# DAC_32CH.net
KiCad netlist of a schematic drawn in Altium Designer
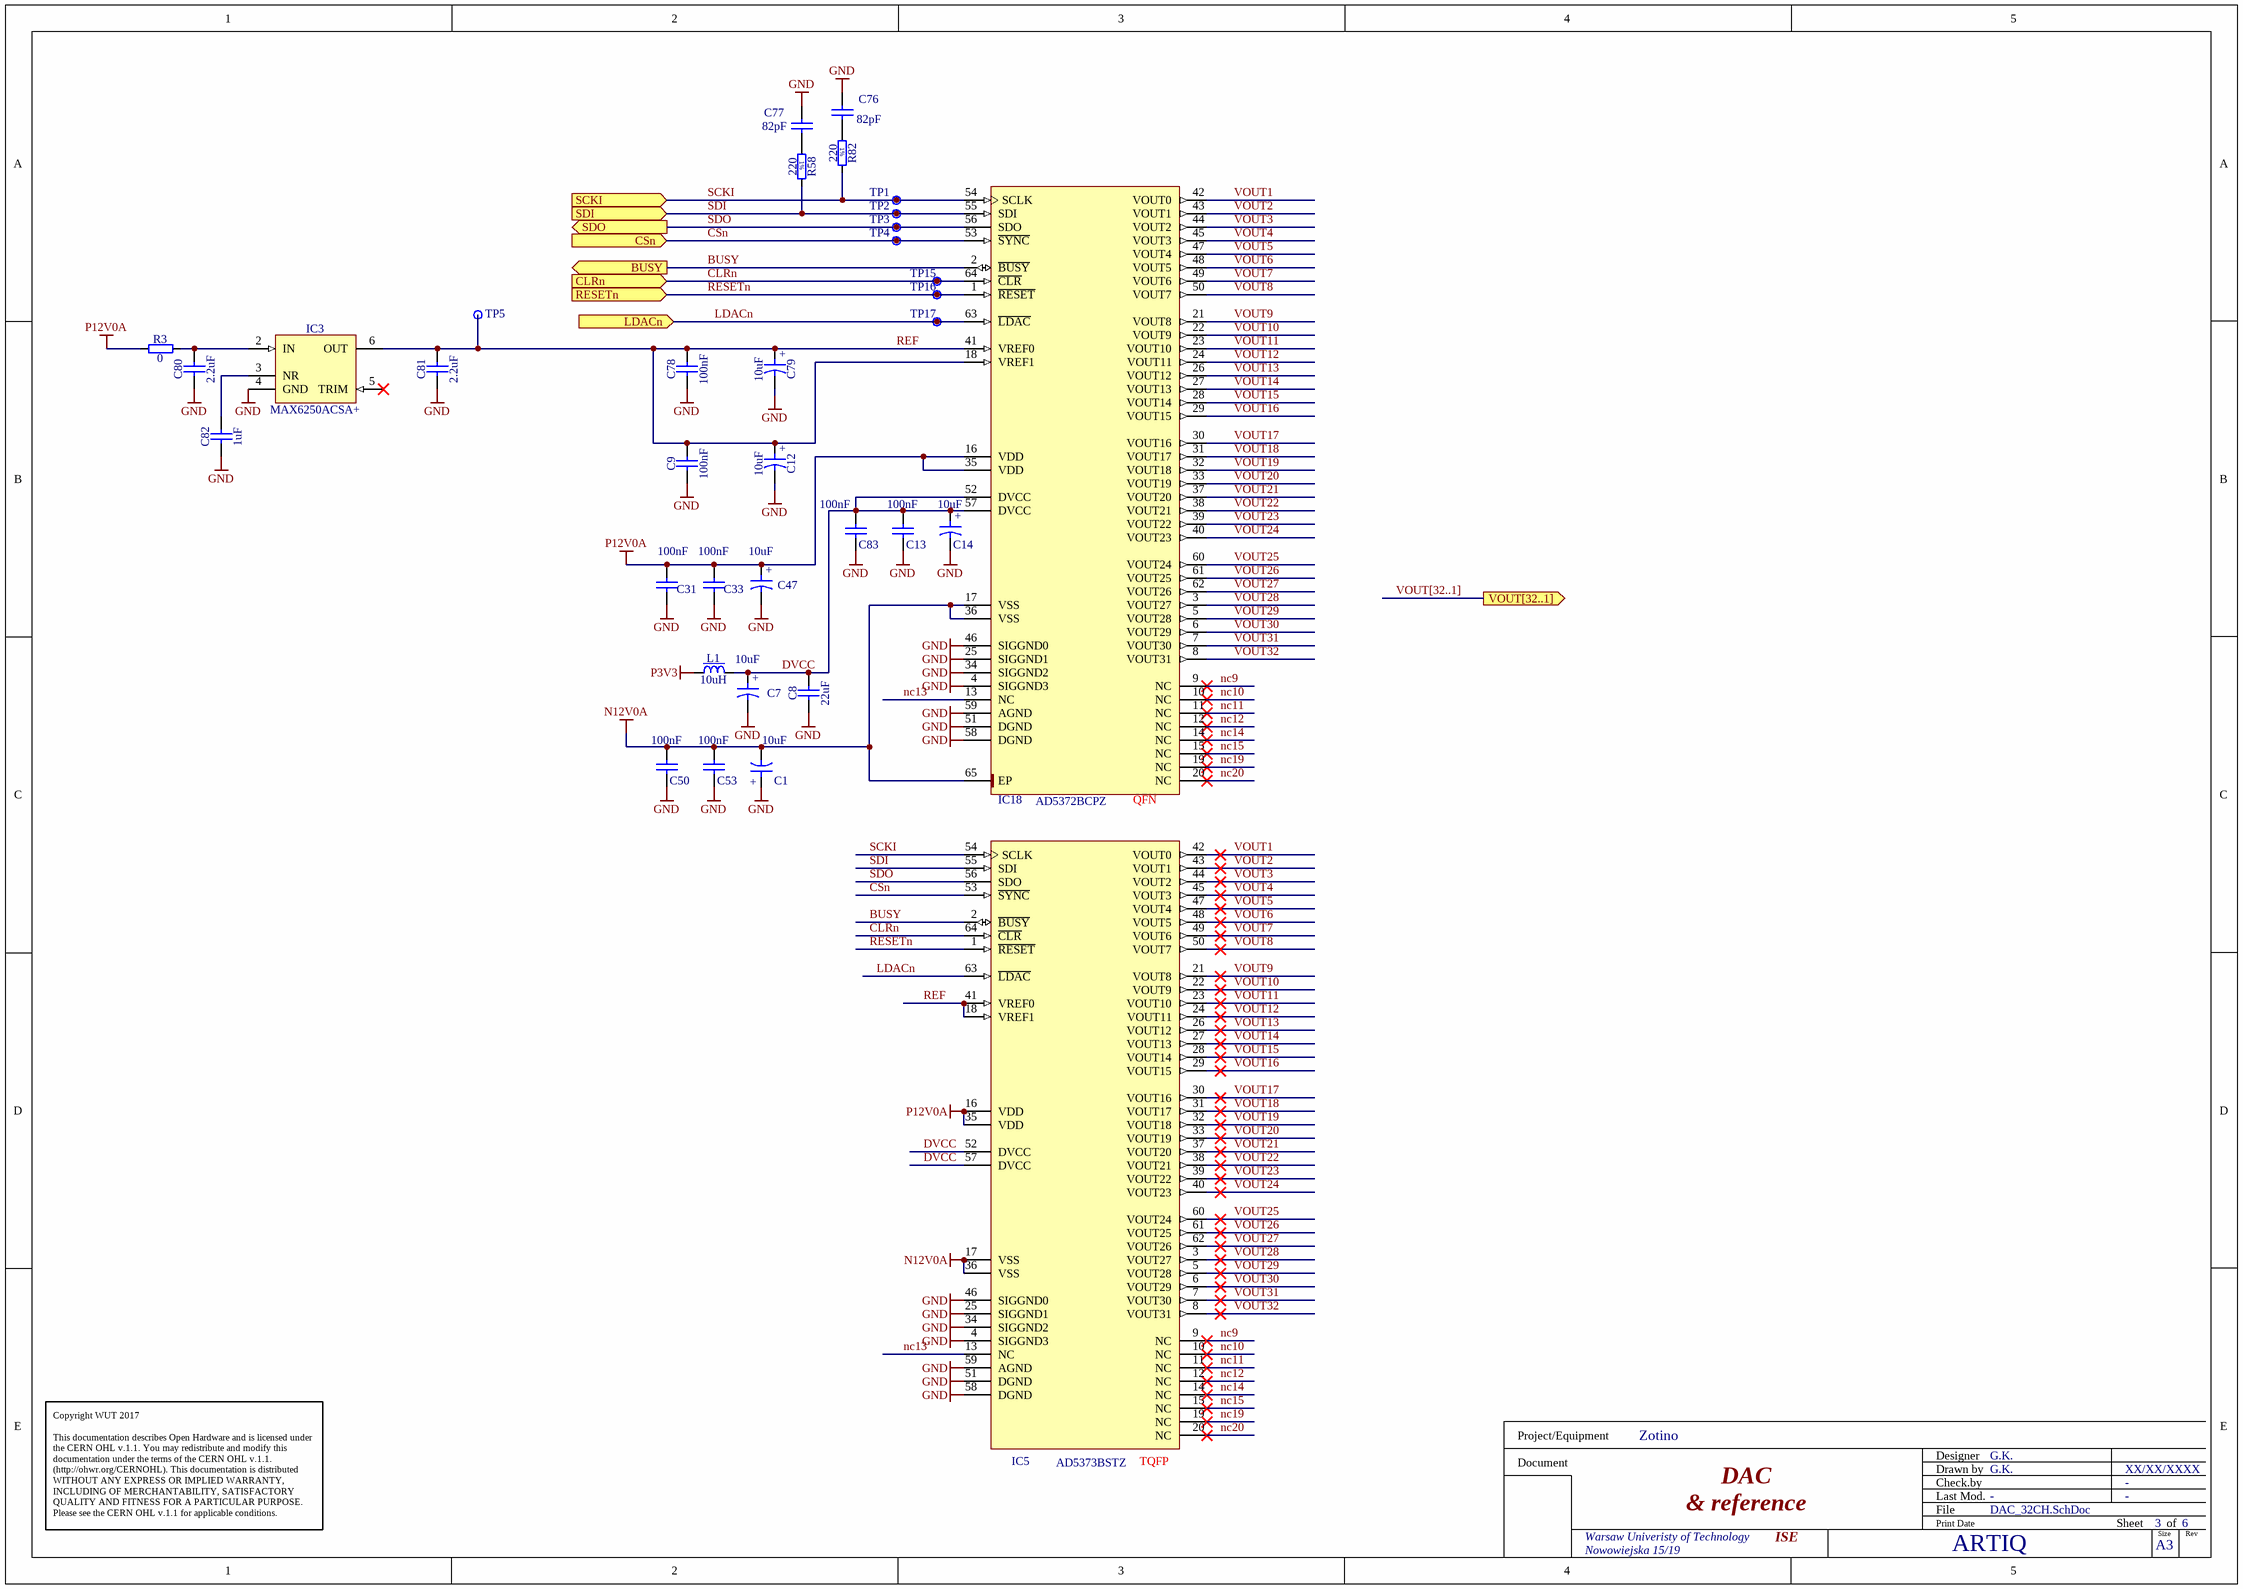
[diagram p0: DAC_32CH.SchDoc]

(export (version "E")
  (design (tool "Eeschema 10.0.6"))
  (components
    (comp (ref "C1")
      (value "10uF")
      (footprint "CAPMP3216X180N")
      (description "Polarised capacitor")
      (fields
        (field (name "PART NUMBER") "CTE3216-18_10UF_16V_20%_AVX_TCJ")
        (field (name "VOLTAGE") "16V")
        (field (name "AUTHOR") "CERN DEM JLC")
      )
      (libsource (lib "Capacitors") (part "Capacitor - polarized"))
    )
    (comp (ref "C7")
      (value "10uF")
      (footprint "CAPMP3216X180N")
      (description "Polarised capacitor")
      (fields
        (field (name "PART NUMBER") "CTE3216-18_10UF_16V_20%_AVX_TCJ")
        (field (name "VOLTAGE") "16V")
        (field (name "AUTHOR") "CERN DEM JLC")
      )
      (libsource (lib "Capacitors") (part "Capacitor - polarized"))
    )
    (comp (ref "C8")
      (value "22uF")
      (footprint "CAPC2012X135N")
      (description "Non-polarised capacitor")
      (fields
        (field (name "PART NUMBER") "CC0805_22UF_16V_10%_X5R")
        (field (name "VOLTAGE") "16V")
        (field (name "AUTHOR") "CERN DEM JLC")
      )
      (libsource (lib "Capacitors") (part "Capacitor - non polarized"))
    )
    (comp (ref "C9")
      (value "100nF")
      (footprint "CAPC1005X55N")
      (description "Non-polarised capacitor")
      (fields
        (field (name "PART NUMBER") "CC0402_100NF_16V_10%_X7R")
        (field (name "VOLTAGE") "16V")
        (field (name "AUTHOR") "CERN DEM JLC")
      )
      (libsource (lib "Capacitors") (part "Capacitor - non polarized"))
    )
    (comp (ref "C12")
      (value "10uF")
      (footprint "CAPMP3216X180N")
      (description "Polarised capacitor")
      (fields
        (field (name "PART NUMBER") "CTE3216-18_10UF_16V_20%_AVX_TCJ")
        (field (name "VOLTAGE") "16V")
        (field (name "AUTHOR") "CERN DEM JLC")
      )
      (libsource (lib "Capacitors") (part "Capacitor - polarized"))
    )
    (comp (ref "C13")
      (value "100nF")
      (footprint "CAPC1005X55N")
      (description "Non-polarised capacitor")
      (fields
        (field (name "PART NUMBER") "CC0402_100NF_16V_10%_X7R")
        (field (name "VOLTAGE") "16V")
        (field (name "AUTHOR") "CERN DEM JLC")
      )
      (libsource (lib "Capacitors") (part "Capacitor - non polarized"))
    )
    (comp (ref "C14")
      (value "10uF")
      (footprint "CAPMP3216X180N")
      (description "Polarised capacitor")
      (fields
        (field (name "PART NUMBER") "CTE3216-18_10UF_16V_20%_AVX_TCJ")
        (field (name "VOLTAGE") "16V")
        (field (name "AUTHOR") "CERN DEM JLC")
      )
      (libsource (lib "Capacitors") (part "Capacitor - polarized"))
    )
    (comp (ref "C31")
      (value "100nF")
      (footprint "CAPC1005X55N")
      (description "Non-polarised capacitor")
      (fields
        (field (name "PART NUMBER") "CC0402_100NF_16V_10%_X7R")
        (field (name "VOLTAGE") "16V")
        (field (name "AUTHOR") "CERN DEM JLC")
      )
      (libsource (lib "Capacitors") (part "Capacitor - non polarized"))
    )
    (comp (ref "C33")
      (value "100nF")
      (footprint "CAPC1005X55N")
      (description "Non-polarised capacitor")
      (fields
        (field (name "PART NUMBER") "CC0402_100NF_16V_10%_X7R")
        (field (name "VOLTAGE") "16V")
        (field (name "AUTHOR") "CERN DEM JLC")
      )
      (libsource (lib "Capacitors") (part "Capacitor - non polarized"))
    )
    (comp (ref "C47")
      (value "10uF")
      (footprint "CAPMP3216X180N")
      (description "Polarised capacitor")
      (fields
        (field (name "PART NUMBER") "CTE3216-18_10UF_16V_20%_AVX_TCJ")
        (field (name "VOLTAGE") "16V")
        (field (name "AUTHOR") "CERN DEM JLC")
      )
      (libsource (lib "Capacitors") (part "Capacitor - polarized"))
    )
    (comp (ref "C50")
      (value "100nF")
      (footprint "CAPC1005X55N")
      (description "Non-polarised capacitor")
      (fields
        (field (name "PART NUMBER") "CC0402_100NF_16V_10%_X7R")
        (field (name "VOLTAGE") "16V")
        (field (name "AUTHOR") "CERN DEM JLC")
      )
      (libsource (lib "Capacitors") (part "Capacitor - non polarized"))
    )
    (comp (ref "C53")
      (value "100nF")
      (footprint "CAPC1005X55N")
      (description "Non-polarised capacitor")
      (fields
        (field (name "PART NUMBER") "CC0402_100NF_16V_10%_X7R")
        (field (name "VOLTAGE") "16V")
        (field (name "AUTHOR") "CERN DEM JLC")
      )
      (libsource (lib "Capacitors") (part "Capacitor - non polarized"))
    )
    (comp (ref "C76")
      (value "82pF")
      (footprint "CAPC1608X87N")
      (description "Non-polarised capacitor")
      (fields
        (field (name "PART NUMBER") "CC0603_82PF_50V_5%_NP0")
        (field (name "VOLTAGE") "50V")
        (field (name "AUTHOR") "CERN DEM JLC")
      )
      (libsource (lib "Capacitors") (part "Capacitor - non polarized"))
    )
    (comp (ref "C77")
      (value "82pF")
      (footprint "CAPC1608X87N")
      (description "Non-polarised capacitor")
      (fields
        (field (name "PART NUMBER") "CC0603_82PF_50V_5%_NP0")
        (field (name "VOLTAGE") "50V")
        (field (name "AUTHOR") "CERN DEM JLC")
      )
      (libsource (lib "Capacitors") (part "Capacitor - non polarized"))
    )
    (comp (ref "C78")
      (value "100nF")
      (footprint "CAPC1005X55N")
      (description "Non-polarised capacitor")
      (fields
        (field (name "PART NUMBER") "CC0402_100NF_16V_10%_X7R")
        (field (name "VOLTAGE") "16V")
        (field (name "AUTHOR") "CERN DEM JLC")
      )
      (libsource (lib "Capacitors") (part "Capacitor - non polarized"))
    )
    (comp (ref "C79")
      (value "10uF")
      (footprint "CAPMP3216X180N")
      (description "Polarised capacitor")
      (fields
        (field (name "PART NUMBER") "CTE3216-18_10UF_16V_20%_AVX_TCJ")
        (field (name "VOLTAGE") "16V")
        (field (name "AUTHOR") "CERN DEM JLC")
      )
      (libsource (lib "Capacitors") (part "Capacitor - polarized"))
    )
    (comp (ref "C80")
      (value "2.2uF")
      (footprint "CAPC1608X87N")
      (description "Non-polarised capacitor")
      (fields
        (field (name "PART NUMBER") "CC0603_2.2UF_16V_10%_X5R")
        (field (name "VOLTAGE") "16V")
        (field (name "AUTHOR") "CERN DEM JLC")
      )
      (libsource (lib "Capacitors") (part "Capacitor - non polarized"))
    )
    (comp (ref "C81")
      (value "2.2uF")
      (footprint "CAPC1608X87N")
      (description "Non-polarised capacitor")
      (fields
        (field (name "PART NUMBER") "CC0603_2.2UF_16V_10%_X5R")
        (field (name "VOLTAGE") "16V")
        (field (name "AUTHOR") "CERN DEM JLC")
      )
      (libsource (lib "Capacitors") (part "Capacitor - non polarized"))
    )
    (comp (ref "C82")
      (value "1uF")
      (footprint "CAPC1608X87N")
      (description "Non-polarised capacitor")
      (fields
        (field (name "PART NUMBER") "CC0603_1UF_25V_10%_X7R")
        (field (name "VOLTAGE") "25V")
        (field (name "AUTHOR") "CERN DEM JLC")
      )
      (libsource (lib "Capacitors") (part "Capacitor - non polarized"))
    )
    (comp (ref "C83")
      (value "100nF")
      (footprint "CAPC1005X55N")
      (description "Non-polarised capacitor")
      (fields
        (field (name "PART NUMBER") "CC0402_100NF_16V_10%_X7R")
        (field (name "VOLTAGE") "16V")
        (field (name "AUTHOR") "CERN DEM JLC")
      )
      (libsource (lib "Capacitors") (part "Capacitor - non polarized"))
    )
    (comp (ref "IC3")
      (value "MAX6250ACSA+")
      (footprint "SOIC127P600X175-8N")
      (description "1ppm/°C, Low-Noise, Precision, +5.000V Voltage Reference")
      (fields (field (name "MANUFACTURER") "MAXIM") (field (name "AUTHOR") "CERN DEM JMW"))
      (libsource (lib "ICs And Semiconductors") (part "MAX6250"))
    )
    (comp (ref "IC5")
      (value "AD5373BSTZ")
      (footprint "TSQFP50P1200X1200X160-64L")
      (description "32-Channel, 16-Bit, Serial Input, Voltage Output Digital-to-Analog Converter")
      (fields (field (name "MANUFACTURER") "ANALOG DEVICES") (field (name "AUTHOR") "GK"))
      (libsource (lib "LIBRARY_SCH") (part "DAC_AD5372_QFP"))
    )
    (comp (ref "IC18")
      (value "AD5372BCPZ")
      (footprint "QFN50P900X900X100-65N-S725")
      (description "32-Channel, 16-Bit, Serial Input, Voltage Output Digital-to-Analog Converter")
      (fields (field (name "MANUFACTURER") "ANALOG DEVICES") (field (name "AUTHOR") "GK"))
      (libsource (lib "LIBRARY_SCH") (part "DAC_AD5372"))
    )
    (comp (ref "L1")
      (value "10uH")
      (footprint "IND_MURATA-PS_8400")
      (description "Inductor With Core")
      (fields
        (field (name "PART NUMBER") "IND_10UH_10%_MURATA-PS_8400")
        (field (name "POWER") "950mA")
        (field (name "AUTHOR") "CERN DEM JLC")
      )
      (libsource (lib "Inductors & Transformers") (part "Inductor With Magnetic core"))
    )
    (comp (ref "R3")
      (value "0")
      (footprint "RESC1005X40N")
      (description "Resistor")
      (fields
        (field (name "PART NUMBER") "R0402_0R_JUMPER")
        (field (name "MANUFACTURER") "GENERIC")
        (field (name "AUTHOR") "CERN DEM JLC")
      )
      (libsource (lib "Resistors") (part "Resistor"))
    )
    (comp (ref "R58")
      (value "220")
      (footprint "RESC1608X55N")
      (description "Resistor - 1%")
      (fields
        (field (name "PART NUMBER") "R0603_220R_1%_0.1W_100PPM")
        (field (name "POWER") "0.1W")
        (field (name "AUTHOR") "CERN DEM JLC")
      )
      (libsource (lib "Resistors") (part "Resistor - 1%"))
    )
    (comp (ref "R82")
      (value "220")
      (footprint "RESC1608X55N")
      (description "Resistor - 1%")
      (fields
        (field (name "PART NUMBER") "R0603_220R_1%_0.1W_100PPM")
        (field (name "POWER") "0.1W")
        (field (name "AUTHOR") "CERN DEM JLC")
      )
      (libsource (lib "Resistors") (part "Resistor - 1%"))
    )
    (comp (ref "TP1")
      (value "Test Point")
      (footprint "TPS127")
      (fields (field (name "PART NUMBER") "SMD_PAD_1.27X1.27MM") (field (name "AUTHOR") "CERN DEM JLC"))
      (libsource (lib "Eletro-mechanical") (part "Test Point"))
    )
    (comp (ref "TP2")
      (value "Test Point")
      (footprint "TPS127")
      (fields (field (name "PART NUMBER") "SMD_PAD_1.27X1.27MM") (field (name "AUTHOR") "CERN DEM JLC"))
      (libsource (lib "Eletro-mechanical") (part "Test Point"))
    )
    (comp (ref "TP3")
      (value "Test Point")
      (footprint "TPS127")
      (fields (field (name "PART NUMBER") "SMD_PAD_1.27X1.27MM") (field (name "AUTHOR") "CERN DEM JLC"))
      (libsource (lib "Eletro-mechanical") (part "Test Point"))
    )
    (comp (ref "TP4")
      (value "Test Point")
      (footprint "TPS127")
      (fields (field (name "PART NUMBER") "SMD_PAD_1.27X1.27MM") (field (name "AUTHOR") "CERN DEM JLC"))
      (libsource (lib "Eletro-mechanical") (part "Test Point"))
    )
    (comp (ref "TP5")
      (value "Test Point")
      (footprint "TPS127")
      (fields (field (name "PART NUMBER") "SMD_PAD_1.27X1.27MM") (field (name "AUTHOR") "CERN DEM JLC"))
      (libsource (lib "Eletro-mechanical") (part "Test Point"))
    )
    (comp (ref "TP15")
      (value "Test Point")
      (footprint "TPS127")
      (fields (field (name "PART NUMBER") "SMD_PAD_1.27X1.27MM") (field (name "AUTHOR") "CERN DEM JLC"))
      (libsource (lib "Eletro-mechanical") (part "Test Point"))
    )
    (comp (ref "TP16")
      (value "Test Point")
      (footprint "TPS127")
      (fields (field (name "PART NUMBER") "SMD_PAD_1.27X1.27MM") (field (name "AUTHOR") "CERN DEM JLC"))
      (libsource (lib "Eletro-mechanical") (part "Test Point"))
    )
    (comp (ref "TP17")
      (value "Test Point")
      (footprint "TPS127")
      (fields (field (name "PART NUMBER") "SMD_PAD_1.27X1.27MM") (field (name "AUTHOR") "CERN DEM JLC"))
      (libsource (lib "Eletro-mechanical") (part "Test Point"))
    )
  )
  (nets
    (net (code "1") (name "/BUSY") (class "Default")
      (node (ref "IC18") (pin "2") (pinfunction "~{BUSY}_2") (pintype "bidirectional"))
      (node (ref "IC5") (pin "2") (pinfunction "~{BUSY}_2") (pintype "bidirectional"))
    )
    (net (code "2") (name "/CLRn") (class "Default")
      (node (ref "IC18") (pin "64") (pinfunction "~{CLR}_64") (pintype "input"))
      (node (ref "IC5") (pin "64") (pinfunction "~{CLR}_64") (pintype "input"))
      (node (ref "TP15") (pin "1") (pinfunction "1_1") (pintype "bidirectional"))
    )
    (net (code "3") (name "/CSn") (class "Default")
      (node (ref "IC18") (pin "53") (pinfunction "~{SYNC}_53") (pintype "input"))
      (node (ref "IC5") (pin "53") (pinfunction "~{SYNC}_53") (pintype "input"))
      (node (ref "TP4") (pin "1") (pinfunction "1_1") (pintype "bidirectional"))
    )
    (net (code "4") (name "/DVCC") (class "Default")
      (node (ref "C13") (pin "2") (pinfunction "2_2") (pintype "passive"))
      (node (ref "C14") (pin "1") (pinfunction "1_1") (pintype "passive"))
      (node (ref "C7") (pin "1") (pinfunction "1_1") (pintype "passive"))
      (node (ref "C8") (pin "2") (pinfunction "2_2") (pintype "passive"))
      (node (ref "C83") (pin "2") (pinfunction "2_2") (pintype "passive"))
      (node (ref "IC18") (pin "52") (pinfunction "DVCC_52") (pintype "power_in"))
      (node (ref "IC18") (pin "57") (pinfunction "DVCC_57") (pintype "power_in"))
      (node (ref "IC5") (pin "52") (pinfunction "DVCC_52") (pintype "power_in"))
      (node (ref "IC5") (pin "57") (pinfunction "DVCC_57") (pintype "power_in"))
      (node (ref "L1") (pin "2") (pinfunction "2_2") (pintype "passive"))
    )
    (net (code "5") (name "/LDACn") (class "Default")
      (node (ref "IC18") (pin "63") (pinfunction "~{LDAC}_63") (pintype "input"))
      (node (ref "IC5") (pin "63") (pinfunction "~{LDAC}_63") (pintype "input"))
      (node (ref "TP17") (pin "1") (pinfunction "1_1") (pintype "bidirectional"))
    )
    (net (code "6") (name "/REF") (class "Default")
      (node (ref "C12") (pin "1") (pinfunction "1_1") (pintype "passive"))
      (node (ref "C78") (pin "2") (pinfunction "2_2") (pintype "passive"))
      (node (ref "C79") (pin "1") (pinfunction "1_1") (pintype "passive"))
      (node (ref "C81") (pin "2") (pinfunction "2_2") (pintype "passive"))
      (node (ref "C9") (pin "2") (pinfunction "2_2") (pintype "passive"))
      (node (ref "IC18") (pin "18") (pinfunction "VREF1_18") (pintype "input"))
      (node (ref "IC18") (pin "41") (pinfunction "VREF0_41") (pintype "input"))
      (node (ref "IC3") (pin "6") (pinfunction "OUT_6") (pintype "power_in"))
      (node (ref "IC5") (pin "18") (pinfunction "VREF1_18") (pintype "input"))
      (node (ref "IC5") (pin "41") (pinfunction "VREF0_41") (pintype "input"))
      (node (ref "TP5") (pin "1") (pinfunction "1_1") (pintype "bidirectional"))
    )
    (net (code "7") (name "/RESETn") (class "Default")
      (node (ref "IC18") (pin "1") (pinfunction "~{RESET}_1") (pintype "input"))
      (node (ref "IC5") (pin "1") (pinfunction "~{RESET}_1") (pintype "input"))
      (node (ref "TP16") (pin "1") (pinfunction "1_1") (pintype "bidirectional"))
    )
    (net (code "8") (name "/SCKI") (class "Default")
      (node (ref "IC18") (pin "54") (pinfunction "SCLK_54") (pintype "input"))
      (node (ref "IC5") (pin "54") (pinfunction "SCLK_54") (pintype "input"))
      (node (ref "R82") (pin "2") (pinfunction "2_2") (pintype "passive"))
      (node (ref "TP1") (pin "1") (pinfunction "1_1") (pintype "bidirectional"))
    )
    (net (code "9") (name "/SDI") (class "Default")
      (node (ref "IC18") (pin "55") (pinfunction "SDI_55") (pintype "input"))
      (node (ref "IC5") (pin "55") (pinfunction "SDI_55") (pintype "input"))
      (node (ref "R58") (pin "2") (pinfunction "2_2") (pintype "passive"))
      (node (ref "TP2") (pin "1") (pinfunction "1_1") (pintype "bidirectional"))
    )
    (net (code "10") (name "/SDO") (class "Default")
      (node (ref "IC18") (pin "56") (pinfunction "SDO_56") (pintype "tri_state"))
      (node (ref "IC5") (pin "56") (pinfunction "SDO_56") (pintype "tri_state"))
      (node (ref "TP3") (pin "1") (pinfunction "1_1") (pintype "bidirectional"))
    )
    (net (code "11") (name "/VOUT1") (class "Default")
      (node (ref "IC18") (pin "42") (pinfunction "VOUT0_42") (pintype "output"))
      (node (ref "IC5") (pin "42") (pinfunction "VOUT0_42") (pintype "output"))
    )
    (net (code "12") (name "/VOUT2") (class "Default")
      (node (ref "IC18") (pin "43") (pinfunction "VOUT1_43") (pintype "output"))
      (node (ref "IC5") (pin "43") (pinfunction "VOUT1_43") (pintype "output"))
    )
    (net (code "13") (name "/VOUT3") (class "Default")
      (node (ref "IC18") (pin "44") (pinfunction "VOUT2_44") (pintype "output"))
      (node (ref "IC5") (pin "44") (pinfunction "VOUT2_44") (pintype "output"))
    )
    (net (code "14") (name "/VOUT4") (class "Default")
      (node (ref "IC18") (pin "45") (pinfunction "VOUT3_45") (pintype "output"))
      (node (ref "IC5") (pin "45") (pinfunction "VOUT3_45") (pintype "output"))
    )
    (net (code "15") (name "/VOUT5") (class "Default")
      (node (ref "IC18") (pin "47") (pinfunction "VOUT4_47") (pintype "output"))
      (node (ref "IC5") (pin "47") (pinfunction "VOUT4_47") (pintype "output"))
    )
    (net (code "16") (name "/VOUT6") (class "Default")
      (node (ref "IC18") (pin "48") (pinfunction "VOUT5_48") (pintype "output"))
      (node (ref "IC5") (pin "48") (pinfunction "VOUT5_48") (pintype "output"))
    )
    (net (code "17") (name "/VOUT7") (class "Default")
      (node (ref "IC18") (pin "49") (pinfunction "VOUT6_49") (pintype "output"))
      (node (ref "IC5") (pin "49") (pinfunction "VOUT6_49") (pintype "output"))
    )
    (net (code "18") (name "/VOUT8") (class "Default")
      (node (ref "IC18") (pin "50") (pinfunction "VOUT7_50") (pintype "output"))
      (node (ref "IC5") (pin "50") (pinfunction "VOUT7_50") (pintype "output"))
    )
    (net (code "19") (name "/VOUT9") (class "Default")
      (node (ref "IC18") (pin "21") (pinfunction "VOUT8_21") (pintype "output"))
      (node (ref "IC5") (pin "21") (pinfunction "VOUT8_21") (pintype "output"))
    )
    (net (code "20") (name "/VOUT10") (class "Default")
      (node (ref "IC18") (pin "22") (pinfunction "VOUT9_22") (pintype "output"))
      (node (ref "IC5") (pin "22") (pinfunction "VOUT9_22") (pintype "output"))
    )
    (net (code "21") (name "/VOUT11") (class "Default")
      (node (ref "IC18") (pin "23") (pinfunction "VOUT10_23") (pintype "output"))
      (node (ref "IC5") (pin "23") (pinfunction "VOUT10_23") (pintype "output"))
    )
    (net (code "22") (name "/VOUT12") (class "Default")
      (node (ref "IC18") (pin "24") (pinfunction "VOUT11_24") (pintype "output"))
      (node (ref "IC5") (pin "24") (pinfunction "VOUT11_24") (pintype "output"))
    )
    (net (code "23") (name "/VOUT13") (class "Default")
      (node (ref "IC18") (pin "26") (pinfunction "VOUT12_26") (pintype "output"))
      (node (ref "IC5") (pin "26") (pinfunction "VOUT12_26") (pintype "output"))
    )
    (net (code "24") (name "/VOUT14") (class "Default")
      (node (ref "IC18") (pin "27") (pinfunction "VOUT13_27") (pintype "output"))
      (node (ref "IC5") (pin "27") (pinfunction "VOUT13_27") (pintype "output"))
    )
    (net (code "25") (name "/VOUT15") (class "Default")
      (node (ref "IC18") (pin "28") (pinfunction "VOUT14_28") (pintype "output"))
      (node (ref "IC5") (pin "28") (pinfunction "VOUT14_28") (pintype "output"))
    )
    (net (code "26") (name "/VOUT16") (class "Default")
      (node (ref "IC18") (pin "29") (pinfunction "VOUT15_29") (pintype "output"))
      (node (ref "IC5") (pin "29") (pinfunction "VOUT15_29") (pintype "output"))
    )
    (net (code "27") (name "/VOUT17") (class "Default")
      (node (ref "IC18") (pin "30") (pinfunction "VOUT16_30") (pintype "output"))
      (node (ref "IC5") (pin "30") (pinfunction "VOUT16_30") (pintype "output"))
    )
    (net (code "28") (name "/VOUT18") (class "Default")
      (node (ref "IC18") (pin "31") (pinfunction "VOUT17_31") (pintype "output"))
      (node (ref "IC5") (pin "31") (pinfunction "VOUT17_31") (pintype "output"))
    )
    (net (code "29") (name "/VOUT19") (class "Default")
      (node (ref "IC18") (pin "32") (pinfunction "VOUT18_32") (pintype "output"))
      (node (ref "IC5") (pin "32") (pinfunction "VOUT18_32") (pintype "output"))
    )
    (net (code "30") (name "/VOUT20") (class "Default")
      (node (ref "IC18") (pin "33") (pinfunction "VOUT19_33") (pintype "output"))
      (node (ref "IC5") (pin "33") (pinfunction "VOUT19_33") (pintype "output"))
    )
    (net (code "31") (name "/VOUT21") (class "Default")
      (node (ref "IC18") (pin "37") (pinfunction "VOUT20_37") (pintype "output"))
      (node (ref "IC5") (pin "37") (pinfunction "VOUT20_37") (pintype "output"))
    )
    (net (code "32") (name "/VOUT22") (class "Default")
      (node (ref "IC18") (pin "38") (pinfunction "VOUT21_38") (pintype "output"))
      (node (ref "IC5") (pin "38") (pinfunction "VOUT21_38") (pintype "output"))
    )
    (net (code "33") (name "/VOUT23") (class "Default")
      (node (ref "IC18") (pin "39") (pinfunction "VOUT22_39") (pintype "output"))
      (node (ref "IC5") (pin "39") (pinfunction "VOUT22_39") (pintype "output"))
    )
    (net (code "34") (name "/VOUT24") (class "Default")
      (node (ref "IC18") (pin "40") (pinfunction "VOUT23_40") (pintype "output"))
      (node (ref "IC5") (pin "40") (pinfunction "VOUT23_40") (pintype "output"))
    )
    (net (code "35") (name "/VOUT25") (class "Default")
      (node (ref "IC18") (pin "60") (pinfunction "VOUT24_60") (pintype "output"))
      (node (ref "IC5") (pin "60") (pinfunction "VOUT24_60") (pintype "output"))
    )
    (net (code "36") (name "/VOUT26") (class "Default")
      (node (ref "IC18") (pin "61") (pinfunction "VOUT25_61") (pintype "output"))
      (node (ref "IC5") (pin "61") (pinfunction "VOUT25_61") (pintype "output"))
    )
    (net (code "37") (name "/VOUT27") (class "Default")
      (node (ref "IC18") (pin "62") (pinfunction "VOUT26_62") (pintype "output"))
      (node (ref "IC5") (pin "62") (pinfunction "VOUT26_62") (pintype "output"))
    )
    (net (code "38") (name "/VOUT28") (class "Default")
      (node (ref "IC18") (pin "3") (pinfunction "VOUT27_3") (pintype "output"))
      (node (ref "IC5") (pin "3") (pinfunction "VOUT27_3") (pintype "output"))
    )
    (net (code "39") (name "/VOUT29") (class "Default")
      (node (ref "IC18") (pin "5") (pinfunction "VOUT28_5") (pintype "output"))
      (node (ref "IC5") (pin "5") (pinfunction "VOUT28_5") (pintype "output"))
    )
    (net (code "40") (name "/VOUT30") (class "Default")
      (node (ref "IC18") (pin "6") (pinfunction "VOUT29_6") (pintype "output"))
      (node (ref "IC5") (pin "6") (pinfunction "VOUT29_6") (pintype "output"))
    )
    (net (code "41") (name "/VOUT31") (class "Default")
      (node (ref "IC18") (pin "7") (pinfunction "VOUT30_7") (pintype "output"))
      (node (ref "IC5") (pin "7") (pinfunction "VOUT30_7") (pintype "output"))
    )
    (net (code "42") (name "/VOUT32") (class "Default")
      (node (ref "IC18") (pin "8") (pinfunction "VOUT31_8") (pintype "output"))
      (node (ref "IC5") (pin "8") (pinfunction "VOUT31_8") (pintype "output"))
    )
    (net (code "44") (name "/nc9") (class "Default")
      (node (ref "IC18") (pin "9") (pinfunction "NC_9") (pintype "passive"))
      (node (ref "IC5") (pin "9") (pinfunction "NC_9") (pintype "passive"))
    )
    (net (code "45") (name "/nc10") (class "Default")
      (node (ref "IC18") (pin "10") (pinfunction "NC_10") (pintype "passive"))
      (node (ref "IC5") (pin "10") (pinfunction "NC_10") (pintype "passive"))
    )
    (net (code "46") (name "/nc11") (class "Default")
      (node (ref "IC18") (pin "11") (pinfunction "NC_11") (pintype "passive"))
      (node (ref "IC5") (pin "11") (pinfunction "NC_11") (pintype "passive"))
    )
    (net (code "47") (name "/nc12") (class "Default")
      (node (ref "IC18") (pin "12") (pinfunction "NC_12") (pintype "passive"))
      (node (ref "IC5") (pin "12") (pinfunction "NC_12") (pintype "passive"))
    )
    (net (code "48") (name "/nc13") (class "Default")
      (node (ref "IC18") (pin "13") (pinfunction "NC_13") (pintype "passive"))
      (node (ref "IC5") (pin "13") (pinfunction "NC_13") (pintype "passive"))
    )
    (net (code "49") (name "/nc14") (class "Default")
      (node (ref "IC18") (pin "14") (pinfunction "NC_14") (pintype "passive"))
      (node (ref "IC5") (pin "14") (pinfunction "NC_14") (pintype "passive"))
    )
    (net (code "50") (name "/nc15") (class "Default")
      (node (ref "IC18") (pin "15") (pinfunction "NC_15") (pintype "passive"))
      (node (ref "IC5") (pin "15") (pinfunction "NC_15") (pintype "passive"))
    )
    (net (code "51") (name "/nc19") (class "Default")
      (node (ref "IC18") (pin "19") (pinfunction "NC_19") (pintype "passive"))
      (node (ref "IC5") (pin "19") (pinfunction "NC_19") (pintype "passive"))
    )
    (net (code "52") (name "/nc20") (class "Default")
      (node (ref "IC18") (pin "20") (pinfunction "NC_20") (pintype "passive"))
      (node (ref "IC5") (pin "20") (pinfunction "NC_20") (pintype "passive"))
    )
    (net (code "53") (name "GND") (class "Default")
      (node (ref "C1") (pin "1") (pinfunction "1_1") (pintype "passive"))
      (node (ref "C12") (pin "2") (pinfunction "2_2") (pintype "passive"))
      (node (ref "C13") (pin "1") (pinfunction "1_1") (pintype "passive"))
      (node (ref "C14") (pin "2") (pinfunction "2_2") (pintype "passive"))
      (node (ref "C31") (pin "1") (pinfunction "1_1") (pintype "passive"))
      (node (ref "C33") (pin "1") (pinfunction "1_1") (pintype "passive"))
      (node (ref "C47") (pin "2") (pinfunction "2_2") (pintype "passive"))
      (node (ref "C50") (pin "1") (pinfunction "1_1") (pintype "passive"))
      (node (ref "C53") (pin "1") (pinfunction "1_1") (pintype "passive"))
      (node (ref "C7") (pin "2") (pinfunction "2_2") (pintype "passive"))
      (node (ref "C76") (pin "1") (pinfunction "1_1") (pintype "passive"))
      (node (ref "C77") (pin "1") (pinfunction "1_1") (pintype "passive"))
      (node (ref "C78") (pin "1") (pinfunction "1_1") (pintype "passive"))
      (node (ref "C79") (pin "2") (pinfunction "2_2") (pintype "passive"))
      (node (ref "C8") (pin "1") (pinfunction "1_1") (pintype "passive"))
      (node (ref "C80") (pin "1") (pinfunction "1_1") (pintype "passive"))
      (node (ref "C81") (pin "1") (pinfunction "1_1") (pintype "passive"))
      (node (ref "C82") (pin "1") (pinfunction "1_1") (pintype "passive"))
      (node (ref "C83") (pin "1") (pinfunction "1_1") (pintype "passive"))
      (node (ref "C9") (pin "1") (pinfunction "1_1") (pintype "passive"))
      (node (ref "IC18") (pin "25") (pinfunction "SIGGND1_25") (pintype "power_in"))
      (node (ref "IC18") (pin "34") (pinfunction "SIGGND2_34") (pintype "power_in"))
      (node (ref "IC18") (pin "4") (pinfunction "SIGGND3_4") (pintype "power_in"))
      (node (ref "IC18") (pin "46") (pinfunction "SIGGND0_46") (pintype "power_in"))
      (node (ref "IC18") (pin "51") (pinfunction "DGND_51") (pintype "power_in"))
      (node (ref "IC18") (pin "58") (pinfunction "DGND_58") (pintype "power_in"))
      (node (ref "IC18") (pin "59") (pinfunction "AGND_59") (pintype "power_in"))
      (node (ref "IC3") (pin "4") (pinfunction "GND_4") (pintype "power_in"))
      (node (ref "IC5") (pin "25") (pinfunction "SIGGND1_25") (pintype "power_in"))
      (node (ref "IC5") (pin "34") (pinfunction "SIGGND2_34") (pintype "power_in"))
      (node (ref "IC5") (pin "4") (pinfunction "SIGGND3_4") (pintype "power_in"))
      (node (ref "IC5") (pin "46") (pinfunction "SIGGND0_46") (pintype "power_in"))
      (node (ref "IC5") (pin "51") (pinfunction "DGND_51") (pintype "power_in"))
      (node (ref "IC5") (pin "58") (pinfunction "DGND_58") (pintype "power_in"))
      (node (ref "IC5") (pin "59") (pinfunction "AGND_59") (pintype "power_in"))
    )
    (net (code "54") (name "N12V0A") (class "Default")
      (node (ref "C1") (pin "2") (pinfunction "2_2") (pintype "passive"))
      (node (ref "C50") (pin "2") (pinfunction "2_2") (pintype "passive"))
      (node (ref "C53") (pin "2") (pinfunction "2_2") (pintype "passive"))
      (node (ref "IC18") (pin "17") (pinfunction "VSS_17") (pintype "power_in"))
      (node (ref "IC18") (pin "36") (pinfunction "VSS_36") (pintype "power_in"))
      (node (ref "IC18") (pin "65") (pinfunction "EP_65") (pintype "power_in"))
      (node (ref "IC5") (pin "17") (pinfunction "VSS_17") (pintype "power_in"))
      (node (ref "IC5") (pin "36") (pinfunction "VSS_36") (pintype "power_in"))
    )
    (net (code "55") (name "Net-(C76-Pad2)") (class "Default")
      (node (ref "C76") (pin "2") (pinfunction "2_2") (pintype "passive"))
      (node (ref "R82") (pin "1") (pinfunction "1_1") (pintype "passive"))
    )
    (net (code "56") (name "Net-(C77-Pad2)") (class "Default")
      (node (ref "C77") (pin "2") (pinfunction "2_2") (pintype "passive"))
      (node (ref "R58") (pin "1") (pinfunction "1_1") (pintype "passive"))
    )
    (net (code "57") (name "Net-(IC3-IN)") (class "Default")
      (node (ref "C80") (pin "2") (pinfunction "2_2") (pintype "passive"))
      (node (ref "IC3") (pin "2") (pinfunction "IN_2") (pintype "input"))
      (node (ref "R3") (pin "2") (pinfunction "2_2") (pintype "passive"))
    )
    (net (code "58") (name "Net-(IC3-NR)") (class "Default")
      (node (ref "C82") (pin "2") (pinfunction "2_2") (pintype "passive"))
      (node (ref "IC3") (pin "3") (pinfunction "NR_3") (pintype "passive"))
    )
    (net (code "59") (name "P3V3") (class "Default")
      (node (ref "L1") (pin "1") (pinfunction "1_1") (pintype "passive"))
    )
    (net (code "60") (name "P12V0A") (class "Default")
      (node (ref "C31") (pin "2") (pinfunction "2_2") (pintype "passive"))
      (node (ref "C33") (pin "2") (pinfunction "2_2") (pintype "passive"))
      (node (ref "C47") (pin "1") (pinfunction "1_1") (pintype "passive"))
      (node (ref "IC18") (pin "16") (pinfunction "VDD_16") (pintype "power_in"))
      (node (ref "IC18") (pin "35") (pinfunction "VDD_35") (pintype "power_in"))
      (node (ref "IC5") (pin "16") (pinfunction "VDD_16") (pintype "power_in"))
      (node (ref "IC5") (pin "35") (pinfunction "VDD_35") (pintype "power_in"))
      (node (ref "R3") (pin "1") (pinfunction "1_1") (pintype "passive"))
    )
    (net (code "61") (name "unconnected-(IC3-TRIM-Pad5)") (class "Default")
      (node (ref "IC3") (pin "5") (pinfunction "TRIM_5") (pintype "input+no_connect"))
    )
  )
)
